# BEP32_90Grad.net
KiCad netlist of a schematic drawn in EAGLE
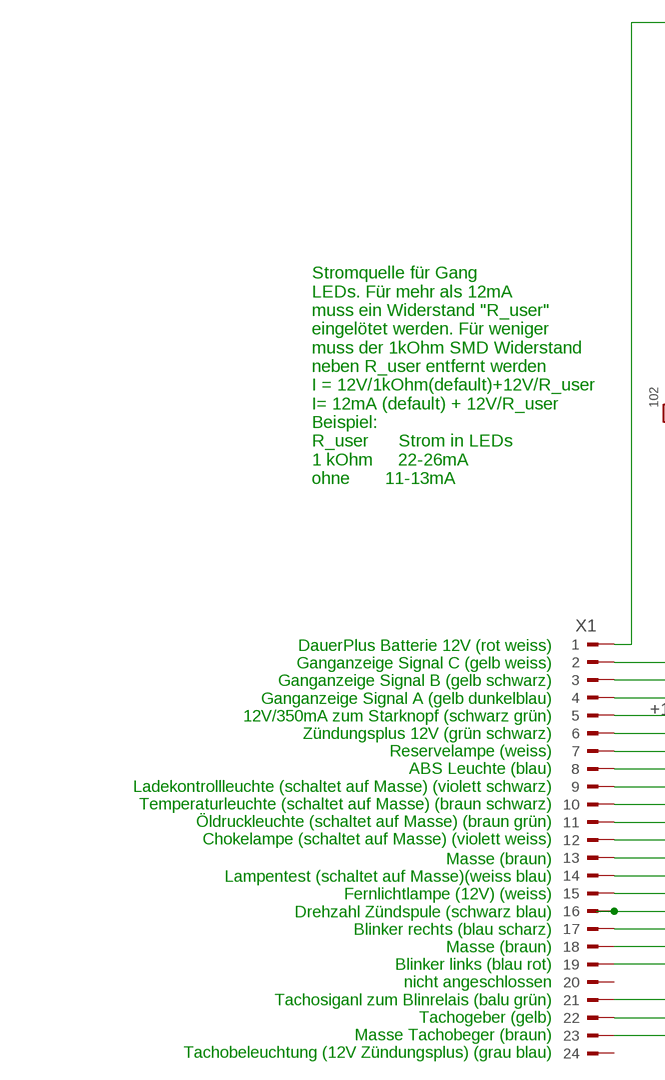
[diagram p0: schematic, sheet 1, part 1 of 2]
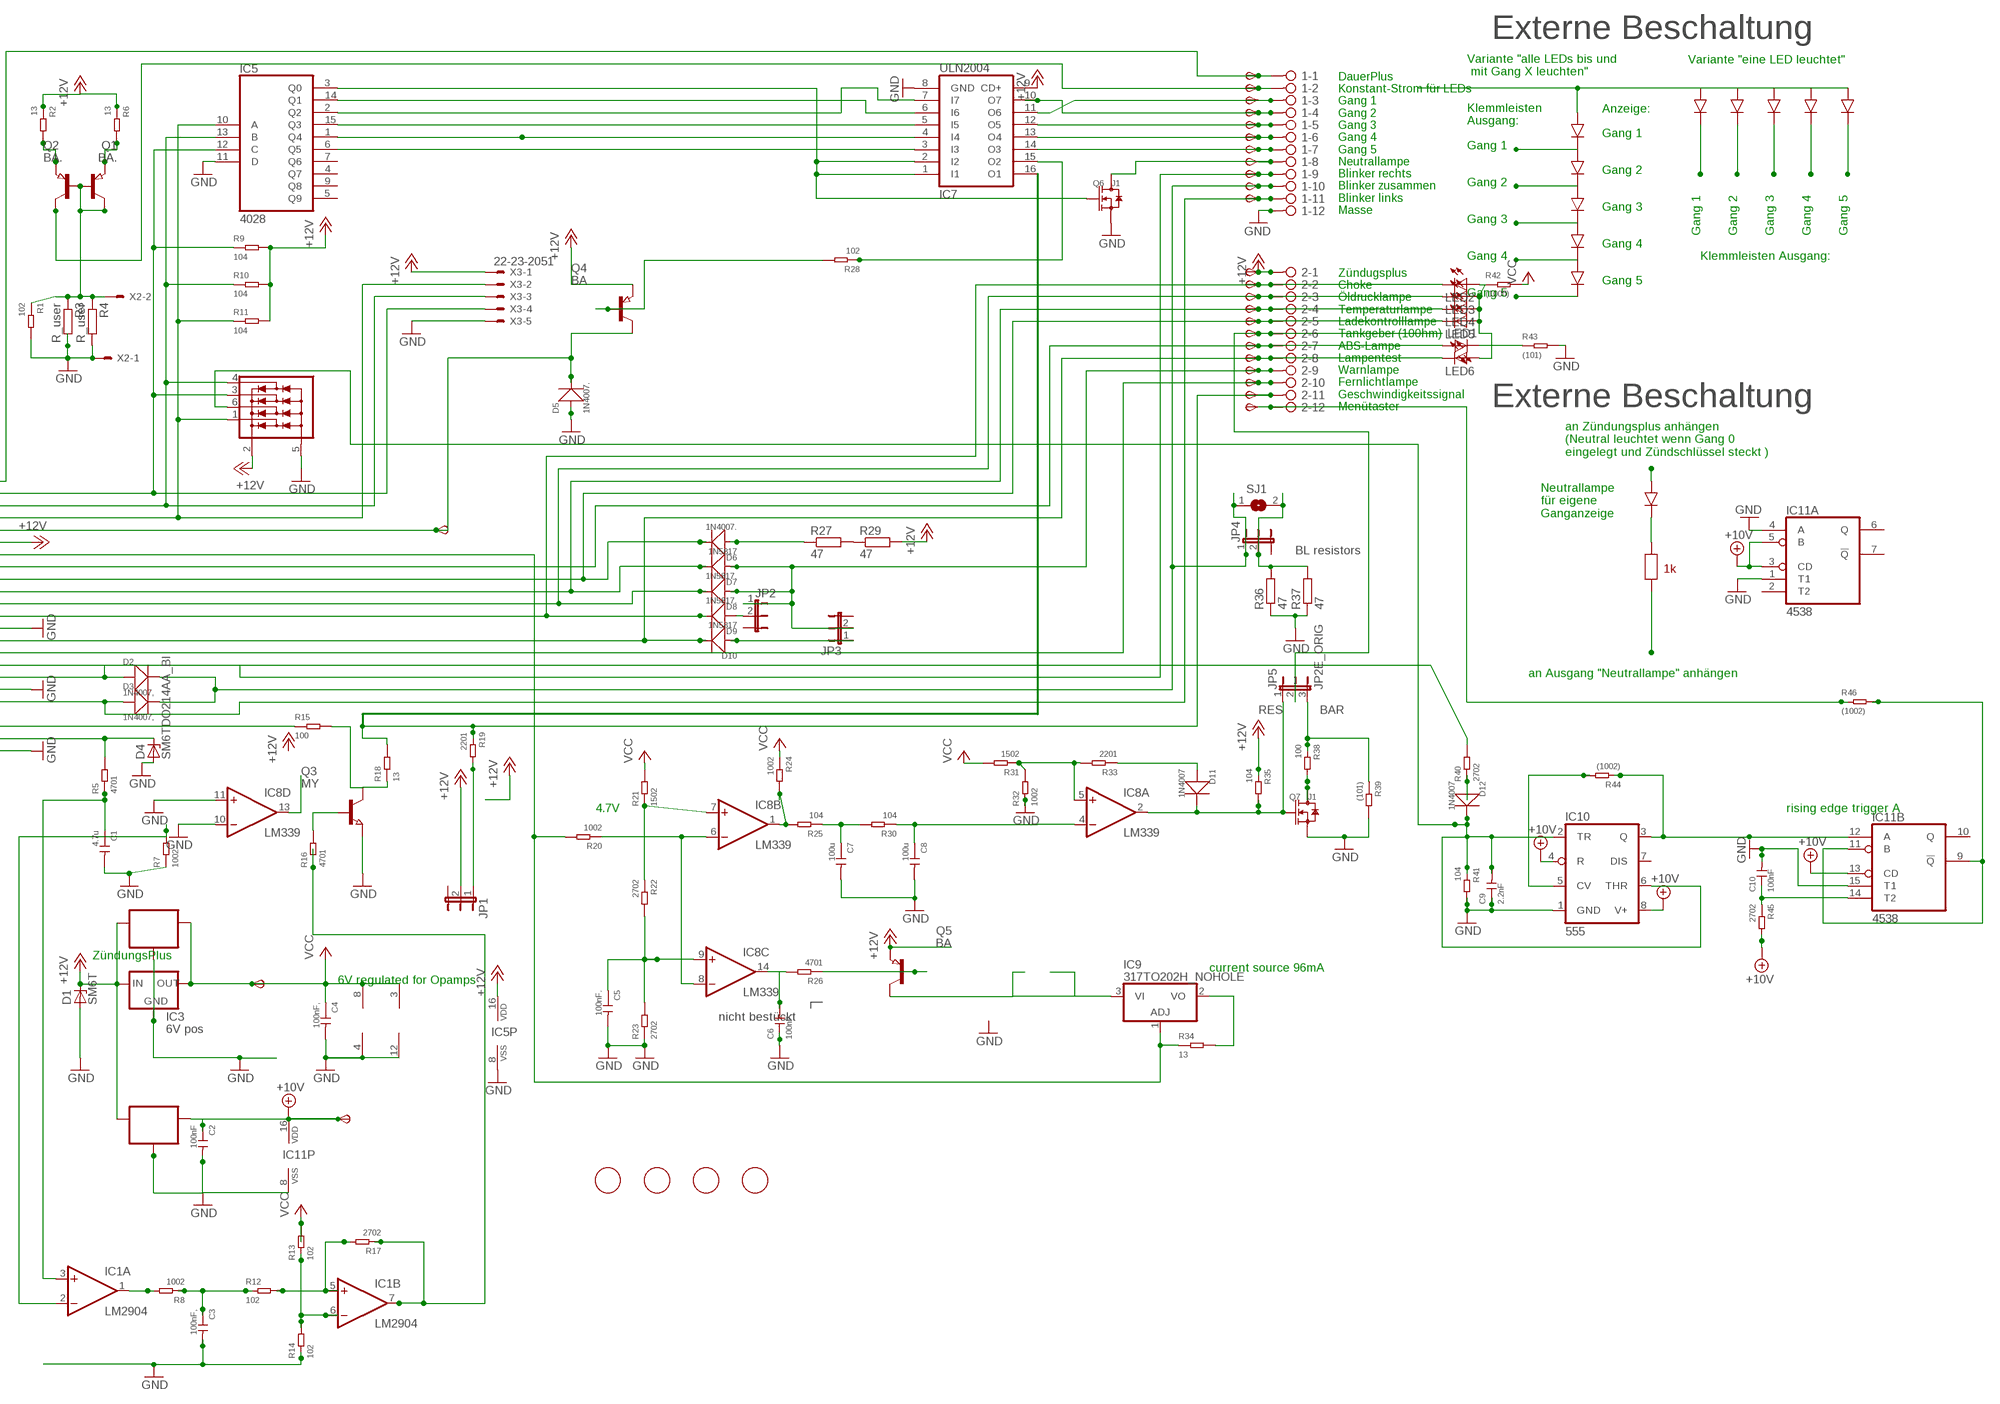
[diagram p1: schematic, sheet 1, part 2 of 2]

(export (version "E")
  (design (tool "Eeschema 10.0.6"))
  (components
    (comp (ref "1")
      (value "2081-1132")
      (footprint "eagle-import:12-PIN")
      (libsource (lib "eagle-import") (part "2081-1132"))
    )
    (comp (ref "2")
      (value "2081-1132")
      (footprint "eagle-import:12-PIN")
      (libsource (lib "eagle-import") (part "2081-1132"))
    )
    (comp (ref "6V")
      (value "TPSB2.0")
      (footprint "eagle-import:B2.0")
      (libsource (lib "eagle-import") (part "TPSB2.0"))
    )
    (comp (ref "10V")
      (value "TPSB2.0")
      (footprint "eagle-import:B2.0")
      (libsource (lib "eagle-import") (part "TPSB2.0"))
    )
    (comp (ref "C1")
      (value "4.7u")
      (footprint "eagle-import:C0805")
      (fields (field (name "MPN") "CC0805KKX5R8BB475"))
      (libsource (lib "eagle-import") (part "CERAMIC-4.7UF-25V-10%-X5R(0805)"))
    )
    (comp (ref "C2")
      (value "100nF")
      (footprint "eagle-import:C0805")
      (fields (field (name "MPN") "CC0805KRX7R9BB104"))
      (libsource (lib "eagle-import") (part "CERAMIC-100NF-50V-10%-X7R(0805)"))
    )
    (comp (ref "C3")
      (value "100nF,")
      (footprint "eagle-import:C0805")
      (fields (field (name "MPN") "CC0805KRX7R9BB104"))
      (libsource (lib "eagle-import") (part "CERAMIC-100NF-50V-10%-X7R(0805)"))
    )
    (comp (ref "C4")
      (value "100nF,")
      (footprint "eagle-import:C0805")
      (fields (field (name "MPN") "CC0805KRX7R9BB104"))
      (libsource (lib "eagle-import") (part "CERAMIC-100NF-50V-10%-X7R(0805)"))
    )
    (comp (ref "C5")
      (value "100nF.")
      (footprint "eagle-import:C0805")
      (fields (field (name "MPN") "CC0805KRX7R9BB104"))
      (libsource (lib "eagle-import") (part "CERAMIC-100NF-50V-10%-X7R(0805)"))
    )
    (comp (ref "C6")
      (value "100nF.")
      (footprint "eagle-import:C0805")
      (fields (field (name "MPN") "CC0805KRX7R9BB104"))
      (libsource (lib "eagle-import") (part "CERAMIC-100NF-50V-10%-X7R(0805)"))
    )
    (comp (ref "C7")
      (value "100u")
      (footprint "eagle-import:C1206")
      (fields (field (name "MPN") "GRM31CR60J107ME39L"))
      (libsource (lib "eagle-import") (part "CERAMIC-100UF-6.3V-20%-X5R(1206)"))
    )
    (comp (ref "C8")
      (value "100u")
      (footprint "eagle-import:C1206")
      (fields (field (name "MPN") "GRM31CR60J107ME39L"))
      (libsource (lib "eagle-import") (part "CERAMIC-100UF-6.3V-20%-X5R(1206)"))
    )
    (comp (ref "C9")
      (value "2.2nF")
      (footprint "eagle-import:C0805")
      (fields (field (name "MPN") "CC0805KRX7R9BB104"))
      (libsource (lib "eagle-import") (part "CERAMIC-100NF-50V-10%-X7R(0805)"))
    )
    (comp (ref "C10")
      (value "100nF")
      (footprint "eagle-import:C0805")
      (fields (field (name "MPN") "CC0805KRX7R9BB104"))
      (libsource (lib "eagle-import") (part "CERAMIC-100NF-50V-10%-X7R(0805)"))
    )
    (comp (ref "D1")
      (value "SM6T")
      (footprint "eagle-import:DO214AA")
      (libsource (lib "eagle-import") (part "SM6T"))
    )
    (comp (ref "D2")
      (value "1N4007,")
      (footprint "eagle-import:DO-214AC")
      (fields (field (name "MPN") "1N4007"))
      (libsource (lib "eagle-import") (part "DIODE-GEN-PURPOSE-1KV-1A(DO-214AC)"))
    )
    (comp (ref "D3")
      (value "1N4007,")
      (footprint "eagle-import:DO-214AC")
      (fields (field (name "MPN") "1N4007"))
      (libsource (lib "eagle-import") (part "DIODE-GEN-PURPOSE-1KV-1A(DO-214AC)"))
    )
    (comp (ref "D4")
      (value "SM6TDO214AA_BI")
      (footprint "eagle-import:DO214AA_BI")
      (libsource (lib "eagle-import") (part "SM6TDO214AA_BI"))
    )
    (comp (ref "D5")
      (value "1N4007.")
      (footprint "eagle-import:DO-214AC")
      (fields (field (name "MPN") "1N4007"))
      (libsource (lib "eagle-import") (part "DIODE-GEN-PURPOSE-1KV-1A(DO-214AC)"))
    )
    (comp (ref "D6")
      (value "1N4007.")
      (footprint "eagle-import:DO-214AC")
      (fields (field (name "MPN") "1N4007"))
      (libsource (lib "eagle-import") (part "DIODE-GEN-PURPOSE-1KV-1A(DO-214AC)"))
    )
    (comp (ref "D7")
      (value "1N5817")
      (footprint "eagle-import:DO-214AC_SLIM")
      (libsource (lib "eagle-import") (part "DIODE-GEN-PURPOSE-1KV-1A(DO-214AC)DO-214AC/1206"))
    )
    (comp (ref "D8")
      (value "1N5817.")
      (footprint "eagle-import:DO-214AC_SLIM")
      (libsource (lib "eagle-import") (part "DIODE-GEN-PURPOSE-1KV-1A(DO-214AC)DO-214AC/1206"))
    )
    (comp (ref "D9")
      (value "1N5817.")
      (footprint "eagle-import:DO-214AC_SLIM")
      (libsource (lib "eagle-import") (part "DIODE-GEN-PURPOSE-1KV-1A(DO-214AC)DO-214AC/1206"))
    )
    (comp (ref "D10")
      (value "1N5817")
      (footprint "eagle-import:DO-214AC_SLIM")
      (libsource (lib "eagle-import") (part "DIODE-GEN-PURPOSE-1KV-1A(DO-214AC)DO-214AC/1206"))
    )
    (comp (ref "D11")
      (value "1N4007")
      (footprint "eagle-import:DO-214AC")
      (libsource (lib "eagle-import") (part "DIODE-GEN-PURPOSE-1KV-1A(DO-214AC)"))
    )
    (comp (ref "D12")
      (value "1N4007")
      (footprint "eagle-import:DO-214AC")
      (libsource (lib "eagle-import") (part "DIODE-GEN-PURPOSE-1KV-1A(DO-214AC)"))
    )
    (comp (ref "FID1")
      (value "FIDUCIAL")
      (footprint "eagle-import:FIDUCIAL_1MM")
      (libsource (lib "eagle-import") (part "FIDUCIAL"))
    )
    (comp (ref "FID2")
      (value "FIDUCIAL")
      (footprint "eagle-import:FIDUCIAL_1MM")
      (libsource (lib "eagle-import") (part "FIDUCIAL"))
    )
    (comp (ref "FID3")
      (value "FIDUCIAL")
      (footprint "eagle-import:FIDUCIAL_1MM")
      (libsource (lib "eagle-import") (part "FIDUCIAL"))
    )
    (comp (ref "FID4")
      (value "FIDUCIAL")
      (footprint "eagle-import:FIDUCIAL_1MM")
      (libsource (lib "eagle-import") (part "FIDUCIAL"))
    )
    (comp (ref "IC1")
      (value "LM2904")
      (footprint "eagle-import:SO08")
      (libsource (lib "eagle-import") (part "LM358D"))
    )
    (comp (ref "IC2")
      (value "78L06")
      (footprint "eagle-import:SOT89_ROUND")
      (libsource (lib "eagle-import") (part "78LXXSOT89_ROUND"))
    )
    (comp (ref "IC3")
      (value "6V pos")
      (footprint "eagle-import:78LXX")
      (libsource (lib "eagle-import") (part "v-reg_78LXX"))
    )
    (comp (ref "IC4")
      (value "78L10")
      (footprint "eagle-import:SOT89_ROUND")
      (libsource (lib "eagle-import") (part "78LXXSOT89_ROUND"))
    )
    (comp (ref "IC5")
      (value "4028")
      (footprint "eagle-import:SO16")
      (libsource (lib "eagle-import") (part "4028D"))
    )
    (comp (ref "IC6")
      (value "NUP4304SOT457_R")
      (footprint "eagle-import:SOT457R_PHILIPS")
      (libsource (lib "eagle-import") (part "NUP4304SOT457_R"))
    )
    (comp (ref "IC7")
      (value "ULN2004")
      (footprint "eagle-import:SO16")
      (libsource (lib "eagle-import") (part "ULN2004AD"))
    )
    (comp (ref "IC8")
      (value "LM339")
      (footprint "eagle-import:SO14")
      (libsource (lib "eagle-import") (part "LM339D"))
    )
    (comp (ref "IC9")
      (value "317TO202H_NOHOLE")
      (footprint "eagle-import:TO220H_NOHOLE")
      (libsource (lib "eagle-import") (part "317TO202H_NOHOLE"))
    )
    (comp (ref "IC10")
      (value "555")
      (footprint "eagle-import:SO08")
      (libsource (lib "eagle-import") (part "555DNE"))
    )
    (comp (ref "IC11")
      (value "4538")
      (footprint "eagle-import:SO16")
      (libsource (lib "eagle-import") (part "4538D"))
    )
    (comp (ref "JP1")
      (value "JP2EJP2_SMALLPADS")
      (footprint "eagle-import:JP2_SMALLPADS")
      (libsource (lib "eagle-import") (part "JP2EJP2_SMALLPADS"))
    )
    (comp (ref "JP2")
      (value "JP2EJP2_SMALLPADS")
      (footprint "eagle-import:JP2_SMALLPADS")
      (libsource (lib "eagle-import") (part "JP2EJP2_SMALLPADS"))
    )
    (comp (ref "JP3")
      (value "JP2EJP2_SMALLPADS")
      (footprint "eagle-import:JP2_SMALLPADS")
      (libsource (lib "eagle-import") (part "JP2EJP2_SMALLPADS"))
    )
    (comp (ref "JP4")
      (value "JP2EJP2_SMALLPADS")
      (footprint "eagle-import:JP2_SMALLPADS")
      (libsource (lib "eagle-import") (part "JP2EJP2_SMALLPADS"))
    )
    (comp (ref "JP5")
      (value "JP2E_ORIG")
      (footprint "eagle-import:JP2_ORIG_SMALLPADS")
      (libsource (lib "eagle-import") (part "JP2E_ORIG"))
    )
    (comp (ref "LED1")
      (value "LEDLD260")
      (footprint "eagle-import:LD260")
      (libsource (lib "eagle-import") (part "LEDLD260"))
    )
    (comp (ref "LED2")
      (value "LEDLD260")
      (footprint "eagle-import:LD260")
      (libsource (lib "eagle-import") (part "LEDLD260"))
    )
    (comp (ref "LED3")
      (value "LEDLD260")
      (footprint "eagle-import:LD260")
      (libsource (lib "eagle-import") (part "LEDLD260"))
    )
    (comp (ref "LED4")
      (value "LEDLD260")
      (footprint "eagle-import:LD260")
      (libsource (lib "eagle-import") (part "LEDLD260"))
    )
    (comp (ref "LED5")
      (value "LEDLD260")
      (footprint "eagle-import:LD260")
      (libsource (lib "eagle-import") (part "LEDLD260"))
    )
    (comp (ref "LED6")
      (value "LEDLD260")
      (footprint "eagle-import:LD260")
      (libsource (lib "eagle-import") (part "LEDLD260"))
    )
    (comp (ref "Q1")
      (value "BA.")
      (footprint "eagle-import:SOT89")
      (libsource (lib "eagle-import") (part "PNP-TRANSISTOR_SOT89"))
    )
    (comp (ref "Q2")
      (value "BA.")
      (footprint "eagle-import:SOT89")
      (libsource (lib "eagle-import") (part "PNP-TRANSISTOR_SOT89"))
    )
    (comp (ref "Q3")
      (value "MY")
      (footprint "eagle-import:SOT89")
      (libsource (lib "eagle-import") (part "NPN-TRANSISTOR_SOT89"))
    )
    (comp (ref "Q4")
      (value "BA")
      (footprint "eagle-import:SOT89")
      (libsource (lib "eagle-import") (part "PNP-TRANSISTOR_SOT89"))
    )
    (comp (ref "Q5")
      (value "BA")
      (footprint "eagle-import:SOT89")
      (libsource (lib "eagle-import") (part "PNP-TRANSISTOR_SOT89"))
    )
    (comp (ref "Q6")
      (value "J1")
      (footprint "eagle-import:SOT-23")
      (fields (field (name "MPN") "BSS138W-7-F"))
      (libsource (lib "eagle-import") (part "SMD-MOSFET-N-CH-50V-200MA-BSS138W-7-F(SOT-23)"))
    )
    (comp (ref "Q7")
      (value "J1")
      (footprint "eagle-import:SOT-23")
      (fields (field (name "MPN") "BSS138W-7-F"))
      (libsource (lib "eagle-import") (part "SMD-MOSFET-N-CH-50V-200MA-BSS138W-7-F(SOT-23)"))
    )
    (comp (ref "R1")
      (value "102")
      (footprint "eagle-import:R0805")
      (fields (field (name "MPN") "RC0805JR-071KL"))
      (libsource (lib "eagle-import") (part "SMD-RES-1K-5%-1/8W(0805)"))
    )
    (comp (ref "R2")
      (value "13")
      (footprint "eagle-import:R1206")
      (fields (field (name "MPN") "RC1206JR-0713RL"))
      (libsource (lib "eagle-import") (part "SMD-RES-13R-5%-1/4W(1206)"))
    )
    (comp (ref "R3")
      (value "R_user")
      (footprint "eagle-import:R0805")
      (libsource (lib "eagle-import") (part "R-EU_R0805"))
    )
    (comp (ref "R4")
      (value "R_user")
      (footprint "eagle-import:R0805")
      (libsource (lib "eagle-import") (part "R-EU_R0805"))
    )
    (comp (ref "R5")
      (value "4701")
      (footprint "eagle-import:R0805")
      (fields (field (name "MPN") "RC0805JR-074K7L"))
      (libsource (lib "eagle-import") (part "SMD-RES-4.7K-5%-1/8W(0805)"))
    )
    (comp (ref "R6")
      (value "13")
      (footprint "eagle-import:R1206")
      (fields (field (name "MPN") "RC1206JR-0713RL"))
      (libsource (lib "eagle-import") (part "SMD-RES-13R-5%-1/4W(1206)"))
    )
    (comp (ref "R7")
      (value "1002")
      (footprint "eagle-import:R0805")
      (fields (field (name "MPN") "RC0805FR-0710KL"))
      (libsource (lib "eagle-import") (part "SMD-RES-10K-1%-1/8W(0805)"))
    )
    (comp (ref "R8")
      (value "1002")
      (footprint "eagle-import:R0805")
      (fields (field (name "MPN") "RC0805FR-0710KL"))
      (libsource (lib "eagle-import") (part "SMD-RES-10K-1%-1/8W(0805)"))
    )
    (comp (ref "R9")
      (value "104")
      (footprint "eagle-import:R0805")
      (fields (field (name "MPN") "RC0805FR-0710KL"))
      (libsource (lib "eagle-import") (part "SMD-RES-10K-1%-1/8W(0805)"))
    )
    (comp (ref "R10")
      (value "104")
      (footprint "eagle-import:R0805")
      (fields (field (name "MPN") "RC0805FR-0710KL"))
      (libsource (lib "eagle-import") (part "SMD-RES-10K-1%-1/8W(0805)"))
    )
    (comp (ref "R11")
      (value "104")
      (footprint "eagle-import:R0805")
      (fields (field (name "MPN") "RC0805FR-0710KL"))
      (libsource (lib "eagle-import") (part "SMD-RES-10K-1%-1/8W(0805)"))
    )
    (comp (ref "R12")
      (value "102")
      (footprint "eagle-import:R0805")
      (fields (field (name "MPN") "RC0805JR-071KL"))
      (libsource (lib "eagle-import") (part "SMD-RES-1K-5%-1/8W(0805)"))
    )
    (comp (ref "R13")
      (value "102")
      (footprint "eagle-import:R0805")
      (fields (field (name "MPN") "RC0805JR-071KL"))
      (libsource (lib "eagle-import") (part "SMD-RES-1K-5%-1/8W(0805)"))
    )
    (comp (ref "R14")
      (value "102")
      (footprint "eagle-import:R0805")
      (fields (field (name "MPN") "RC0805JR-071KL"))
      (libsource (lib "eagle-import") (part "SMD-RES-1K-5%-1/8W(0805)"))
    )
    (comp (ref "R15")
      (value "100")
      (footprint "eagle-import:R0805")
      (fields (field (name "MPN") "RC0805JR-07220RL"))
      (libsource (lib "eagle-import") (part "SMD-RES-220R-5%-1/8W(0805)"))
    )
    (comp (ref "R16")
      (value "4701")
      (footprint "eagle-import:R0805")
      (fields (field (name "MPN") "RC0805JR-074K7L"))
      (libsource (lib "eagle-import") (part "SMD-RES-4.7K-5%-1/8W(0805)"))
    )
    (comp (ref "R17")
      (value "2702")
      (footprint "eagle-import:R0805")
      (fields (field (name "MPN") "RC0805JR-074K7L"))
      (libsource (lib "eagle-import") (part "SMD-RES-4.7K-5%-1/8W(0805)"))
    )
    (comp (ref "R18")
      (value "13")
      (footprint "eagle-import:R1206")
      (fields (field (name "MPN") "RC1206JR-0713RL"))
      (libsource (lib "eagle-import") (part "SMD-RES-13R-5%-1/4W(1206)"))
    )
    (comp (ref "R19")
      (value "2201")
      (footprint "eagle-import:R0805")
      (fields (field (name "MPN") "RC0805JR-072K2L"))
      (libsource (lib "eagle-import") (part "SMD-RES-2.2K-5%-1/8W(0805)"))
    )
    (comp (ref "R20")
      (value "1002")
      (footprint "eagle-import:R0805")
      (fields (field (name "MPN") "RC0805FR-0710KL"))
      (libsource (lib "eagle-import") (part "SMD-RES-10K-1%-1/8W(0805)"))
    )
    (comp (ref "R21")
      (value "1502")
      (footprint "eagle-import:R0805")
      (fields (field (name "MPN") "RC0805FR-0710KL"))
      (libsource (lib "eagle-import") (part "SMD-RES-10K-1%-1/8W(0805)"))
    )
    (comp (ref "R22")
      (value "2702")
      (footprint "eagle-import:R0805")
      (fields (field (name "MPN") "RC0805JR-074K7L"))
      (libsource (lib "eagle-import") (part "SMD-RES-4.7K-5%-1/8W(0805)"))
    )
    (comp (ref "R23")
      (value "2702")
      (footprint "eagle-import:R0805")
      (fields (field (name "MPN") "RC0805JR-074K7L"))
      (libsource (lib "eagle-import") (part "SMD-RES-4.7K-5%-1/8W(0805)"))
    )
    (comp (ref "R24")
      (value "1002")
      (footprint "eagle-import:R0805")
      (fields (field (name "MPN") "RC0805FR-0710KL"))
      (libsource (lib "eagle-import") (part "SMD-RES-10K-1%-1/8W(0805)"))
    )
    (comp (ref "R25")
      (value "104")
      (footprint "eagle-import:R0805")
      (fields (field (name "MPN") "RC0805FR-0710KL"))
      (libsource (lib "eagle-import") (part "SMD-RES-10K-1%-1/8W(0805)"))
    )
    (comp (ref "R26")
      (value "4701")
      (footprint "eagle-import:R0805")
      (fields (field (name "MPN") "RC0805JR-074K7L"))
      (libsource (lib "eagle-import") (part "SMD-RES-4.7K-5%-1/8W(0805)"))
    )
    (comp (ref "R27")
      (value "47")
      (footprint "eagle-import:V235_17_1MM")
      (libsource (lib "eagle-import") (part "R-EU_V235/17_1MM"))
    )
    (comp (ref "R28")
      (value "102")
      (footprint "eagle-import:R0805")
      (fields (field (name "MPN") "RC0805JR-071KL"))
      (libsource (lib "eagle-import") (part "SMD-RES-1K-5%-1/8W(0805)"))
    )
    (comp (ref "R29")
      (value "47")
      (footprint "eagle-import:V235_17_1MM")
      (libsource (lib "eagle-import") (part "R-EU_V235/17_1MM"))
    )
    (comp (ref "R30")
      (value "104")
      (footprint "eagle-import:R0805")
      (fields (field (name "MPN") "RC0805FR-0710KL"))
      (libsource (lib "eagle-import") (part "SMD-RES-10K-1%-1/8W(0805)"))
    )
    (comp (ref "R31")
      (value "1502")
      (footprint "eagle-import:R0805")
      (fields (field (name "MPN") "RC0805FR-0710KL"))
      (libsource (lib "eagle-import") (part "SMD-RES-10K-1%-1/8W(0805)"))
    )
    (comp (ref "R32")
      (value "1002")
      (footprint "eagle-import:R0805")
      (fields (field (name "MPN") "RC0805FR-0710KL"))
      (libsource (lib "eagle-import") (part "SMD-RES-10K-1%-1/8W(0805)"))
    )
    (comp (ref "R33")
      (value "2201")
      (footprint "eagle-import:R0805")
      (fields (field (name "MPN") "RC0805JR-072K2L"))
      (libsource (lib "eagle-import") (part "SMD-RES-2.2K-5%-1/8W(0805)"))
    )
    (comp (ref "R34")
      (value "13")
      (footprint "eagle-import:R1206")
      (fields (field (name "MPN") "RC1206JR-0713RL"))
      (libsource (lib "eagle-import") (part "SMD-RES-13R-5%-1/4W(1206)"))
    )
    (comp (ref "R35")
      (value "104")
      (footprint "eagle-import:R0805")
      (fields (field (name "MPN") "RC0805FR-0710KL"))
      (libsource (lib "eagle-import") (part "SMD-RES-10K-1%-1/8W(0805)"))
    )
    (comp (ref "R36")
      (value "47")
      (footprint "eagle-import:V235_17_1MM")
      (libsource (lib "eagle-import") (part "R-EU_V235/17_1MM"))
    )
    (comp (ref "R37")
      (value "47")
      (footprint "eagle-import:V235_17_1MM")
      (libsource (lib "eagle-import") (part "R-EU_V235/17_1MM"))
    )
    (comp (ref "R38")
      (value "100")
      (footprint "eagle-import:R0805")
      (fields (field (name "MPN") "RC0805JR-072K2L"))
      (libsource (lib "eagle-import") (part "SMD-RES-2.2K-5%-1/8W(0805)"))
    )
    (comp (ref "R39")
      (value "(101)")
      (footprint "eagle-import:R0805")
      (fields (field (name "MPN") "RC0805JR-072K2L"))
      (libsource (lib "eagle-import") (part "SMD-RES-2.2K-5%-1/8W(0805)"))
    )
    (comp (ref "R40")
      (value "2702")
      (footprint "eagle-import:R0805")
      (fields (field (name "MPN") "RC0805FR-0710KL"))
      (libsource (lib "eagle-import") (part "SMD-RES-10K-1%-1/8W(0805)"))
    )
    (comp (ref "R41")
      (value "104")
      (footprint "eagle-import:R0805")
      (fields (field (name "MPN") "RC0805FR-0710KL"))
      (libsource (lib "eagle-import") (part "SMD-RES-10K-1%-1/8W(0805)"))
    )
    (comp (ref "R42")
      (value "(1000)")
      (footprint "eagle-import:R0805")
      (fields (field (name "MPN") "RC0805JR-07100RL"))
      (libsource (lib "eagle-import") (part "SMD-RES-100R-5%-1/8W(0805)"))
    )
    (comp (ref "R43")
      (value "(101)")
      (footprint "eagle-import:R0805")
      (fields (field (name "MPN") "RC0805JR-07100RL"))
      (libsource (lib "eagle-import") (part "SMD-RES-100R-5%-1/8W(0805)"))
    )
    (comp (ref "R44")
      (value "(1002)")
      (footprint "eagle-import:R0805")
      (fields (field (name "MPN") "RC0805FR-0710KL"))
      (libsource (lib "eagle-import") (part "SMD-RES-10K-1%-1/8W(0805)"))
    )
    (comp (ref "R45")
      (value "2702")
      (footprint "eagle-import:R0805")
      (fields (field (name "MPN") "RC0805JR-074K7L"))
      (libsource (lib "eagle-import") (part "SMD-RES-4.7K-5%-1/8W(0805)"))
    )
    (comp (ref "R46")
      (value "(1002)")
      (footprint "eagle-import:R0805")
      (fields (field (name "MPN") "RC0805JR-074K7L"))
      (libsource (lib "eagle-import") (part "SMD-RES-4.7K-5%-1/8W(0805)"))
    )
    (comp (ref "SJ1") (value "SJ") (footprint "eagle-import:SJ") (libsource (lib "eagle-import") (part "SJ")))
    (comp (ref "START")
      (value "TPSB2.0")
      (footprint "eagle-import:B2.0")
      (libsource (lib "eagle-import") (part "TPSB2.0"))
    )
    (comp (ref "TP1")
      (value "TPSB2.0")
      (footprint "eagle-import:B2.0")
      (libsource (lib "eagle-import") (part "TPSB2.0"))
    )
    (comp (ref "TP2")
      (value "TPSB2.0")
      (footprint "eagle-import:B2.0")
      (libsource (lib "eagle-import") (part "TPSB2.0"))
    )
    (comp (ref "TP3")
      (value "TPSB2.0")
      (footprint "eagle-import:B2.0")
      (libsource (lib "eagle-import") (part "TPSB2.0"))
    )
    (comp (ref "TP4")
      (value "TPSB2.0")
      (footprint "eagle-import:B2.0")
      (libsource (lib "eagle-import") (part "TPSB2.0"))
    )
    (comp (ref "TP5")
      (value "TPSB2.0")
      (footprint "eagle-import:B2.0")
      (libsource (lib "eagle-import") (part "TPSB2.0"))
    )
    (comp (ref "TP6")
      (value "TPSB2.0")
      (footprint "eagle-import:B2.0")
      (libsource (lib "eagle-import") (part "TPSB2.0"))
    )
    (comp (ref "TP7")
      (value "TPSB2.0")
      (footprint "eagle-import:B2.0")
      (libsource (lib "eagle-import") (part "TPSB2.0"))
    )
    (comp (ref "TP8")
      (value "TPSB2.0")
      (footprint "eagle-import:B2.0")
      (libsource (lib "eagle-import") (part "TPSB2.0"))
    )
    (comp (ref "TP9")
      (value "TPSB2.0")
      (footprint "eagle-import:B2.0")
      (libsource (lib "eagle-import") (part "TPSB2.0"))
    )
    (comp (ref "TP10")
      (value "TPSB2.0")
      (footprint "eagle-import:B2.0")
      (libsource (lib "eagle-import") (part "TPSB2.0"))
    )
    (comp (ref "TP11")
      (value "TPSB2.0")
      (footprint "eagle-import:B2.0")
      (libsource (lib "eagle-import") (part "TPSB2.0"))
    )
    (comp (ref "TP12")
      (value "TPSB2.0")
      (footprint "eagle-import:B2.0")
      (libsource (lib "eagle-import") (part "TPSB2.0"))
    )
    (comp (ref "TP13")
      (value "TPSB2.0")
      (footprint "eagle-import:B2.0")
      (libsource (lib "eagle-import") (part "TPSB2.0"))
    )
    (comp (ref "TP16")
      (value "TPSB2.0")
      (footprint "eagle-import:B2.0")
      (libsource (lib "eagle-import") (part "TPSB2.0"))
    )
    (comp (ref "TP17")
      (value "TPSB2.0")
      (footprint "eagle-import:B2.0")
      (libsource (lib "eagle-import") (part "TPSB2.0"))
    )
    (comp (ref "TP18")
      (value "TPSB2.0")
      (footprint "eagle-import:B2.0")
      (libsource (lib "eagle-import") (part "TPSB2.0"))
    )
    (comp (ref "TP19")
      (value "TPSB2.0")
      (footprint "eagle-import:B2.0")
      (libsource (lib "eagle-import") (part "TPSB2.0"))
    )
    (comp (ref "TP21")
      (value "TPSB2.0")
      (footprint "eagle-import:B2.0")
      (libsource (lib "eagle-import") (part "TPSB2.0"))
    )
    (comp (ref "TP22")
      (value "TPSB2.0")
      (footprint "eagle-import:B2.0")
      (libsource (lib "eagle-import") (part "TPSB2.0"))
    )
    (comp (ref "TP23")
      (value "TPSB2.0")
      (footprint "eagle-import:B2.0")
      (libsource (lib "eagle-import") (part "TPSB2.0"))
    )
    (comp (ref "TP24")
      (value "TPSB1,27")
      (footprint "eagle-import:B1,27")
      (libsource (lib "eagle-import") (part "TPSB1,27"))
    )
    (comp (ref "TP25")
      (value "TPSB2.0")
      (footprint "eagle-import:B2.0")
      (libsource (lib "eagle-import") (part "TPSB2.0"))
    )
    (comp (ref "TP26")
      (value "TPSB2.0")
      (footprint "eagle-import:B2.0")
      (libsource (lib "eagle-import") (part "TPSB2.0"))
    )
    (comp (ref "X1")
      (value "CON_BMWV2")
      (footprint "eagle-import:24-PIN_V2")
      (libsource (lib "eagle-import") (part "CON_BMWV2"))
    )
    (comp (ref "X2")
      (value "22-23-2021")
      (footprint "eagle-import:22-23-2021")
      (fields (field (name "MF") "MOLEX"))
      (libsource (lib "eagle-import") (part "22-23-2021"))
    )
    (comp (ref "X3")
      (value "22-23-2051")
      (footprint "eagle-import:22-23-2051")
      (fields (field (name "MF") "MOLEX"))
      (libsource (lib "eagle-import") (part "22-23-2051"))
    )
  )
  (nets
    (net (code "1") (name "+10V") (class "Default")
      (node (ref "10V") (pin "TP") (pinfunction "PP_TP") (pintype "input"))
      (node (ref "C2") (pin "1") (pinfunction "1_1") (pintype "passive"))
      (node (ref "IC10") (pin "4") (pinfunction "R_4") (pintype "input"))
      (node (ref "IC10") (pin "8") (pinfunction "V+_8") (pintype "power_in"))
      (node (ref "IC11") (pin "13") (pinfunction "CD_13") (pintype "input"))
      (node (ref "IC11") (pin "16") (pinfunction "VDD_16") (pintype "power_in"))
      (node (ref "IC11") (pin "3") (pinfunction "CD_3") (pintype "input"))
      (node (ref "IC11") (pin "5") (pinfunction "B_5") (pintype "input"))
      (node (ref "IC4") (pin "1") (pinfunction "OUT_1") (pintype "passive"))
      (node (ref "R45") (pin "2") (pinfunction "2_2") (pintype "passive"))
    )
    (net (code "2") (name "+12V") (class "Default")
      (node (ref "2") (pin "1") (pinfunction "KL_1") (pintype "passive"))
      (node (ref "D1") (pin "C") (pinfunction "C_C") (pintype "passive"))
      (node (ref "IC2") (pin "3") (pinfunction "IN_3") (pintype "input"))
      (node (ref "IC3") (pin "IN") (pinfunction "IN_IN") (pintype "input"))
      (node (ref "IC4") (pin "3") (pinfunction "IN_3") (pintype "input"))
      (node (ref "IC5") (pin "16") (pinfunction "VDD_16") (pintype "power_in"))
      (node (ref "IC6") (pin "2") (pinfunction "V+_2") (pintype "passive"))
      (node (ref "IC7") (pin "9") (pinfunction "CD+_9") (pintype "passive"))
      (node (ref "JP1") (pin "2") (pinfunction "2_2") (pintype "passive"))
      (node (ref "Q4") (pin "3") (pinfunction "E_3") (pintype "passive"))
      (node (ref "Q5") (pin "3") (pinfunction "E_3") (pintype "passive"))
      (node (ref "R10") (pin "2") (pinfunction "2_2") (pintype "passive"))
      (node (ref "R11") (pin "2") (pinfunction "2_2") (pintype "passive"))
      (node (ref "R2") (pin "1") (pinfunction "1_1") (pintype "passive"))
      (node (ref "R29") (pin "2") (pinfunction "2_2") (pintype "passive"))
      (node (ref "R35") (pin "1") (pinfunction "1_1") (pintype "passive"))
      (node (ref "R6") (pin "1") (pinfunction "1_1") (pintype "passive"))
      (node (ref "R9") (pin "2") (pinfunction "2_2") (pintype "passive"))
      (node (ref "TP12") (pin "TP") (pinfunction "PP_TP") (pintype "input"))
      (node (ref "X1") (pin "6") (pinfunction "6_6") (pintype "passive"))
      (node (ref "X3") (pin "1") (pinfunction "S_1") (pintype "passive"))
    )
    (net (code "3") (name "GND") (class "Default")
      (node (ref "1") (pin "12") (pinfunction "KL_12") (pintype "passive"))
      (node (ref "C1") (pin "2") (pinfunction "2_2") (pintype "passive"))
      (node (ref "C10") (pin "2") (pinfunction "2_2") (pintype "passive"))
      (node (ref "C2") (pin "2") (pinfunction "2_2") (pintype "passive"))
      (node (ref "C3") (pin "2") (pinfunction "2_2") (pintype "passive"))
      (node (ref "C4") (pin "2") (pinfunction "2_2") (pintype "passive"))
      (node (ref "C5") (pin "2") (pinfunction "2_2") (pintype "passive"))
      (node (ref "C6") (pin "1") (pinfunction "1_1") (pintype "passive"))
      (node (ref "C7") (pin "2") (pinfunction "2_2") (pintype "passive"))
      (node (ref "C8") (pin "2") (pinfunction "2_2") (pintype "passive"))
      (node (ref "C9") (pin "1") (pinfunction "1_1") (pintype "passive"))
      (node (ref "D1") (pin "A") (pinfunction "A_A") (pintype "passive"))
      (node (ref "D4") (pin "A") (pinfunction "A_A") (pintype "passive"))
      (node (ref "D5") (pin "1") (pinfunction "+_1") (pintype "passive"))
      (node (ref "IC1") (pin "4") (pinfunction "V-_4") (pintype "power_in"))
      (node (ref "IC10") (pin "1") (pinfunction "GND_1") (pintype "power_in"))
      (node (ref "IC11") (pin "1") (pinfunction "T1_1") (pintype "input"))
      (node (ref "IC11") (pin "15") (pinfunction "T1_15") (pintype "input"))
      (node (ref "IC11") (pin "4") (pinfunction "A_4") (pintype "input"))
      (node (ref "IC11") (pin "8") (pinfunction "VSS_8") (pintype "power_in"))
      (node (ref "IC2") (pin "2") (pinfunction "GND_2") (pintype "input"))
      (node (ref "IC2") (pin "2@1") (pinfunction "GND_2@1") (pintype "input"))
      (node (ref "IC3") (pin "GND") (pinfunction "GND_GND") (pintype "input"))
      (node (ref "IC4") (pin "2") (pinfunction "GND_2") (pintype "input"))
      (node (ref "IC4") (pin "2@1") (pinfunction "GND_2@1") (pintype "input"))
      (node (ref "IC5") (pin "11") (pinfunction "D_11") (pintype "input"))
      (node (ref "IC5") (pin "8") (pinfunction "VSS_8") (pintype "power_in"))
      (node (ref "IC6") (pin "5") (pinfunction "V-_5") (pintype "passive"))
      (node (ref "IC7") (pin "8") (pinfunction "GND_8") (pintype "power_in"))
      (node (ref "IC8") (pin "10") (pinfunction "-IN_10") (pintype "input"))
      (node (ref "IC8") (pin "11") (pinfunction "+IN_11") (pintype "input"))
      (node (ref "IC8") (pin "12") (pinfunction "GND_12") (pintype "power_in"))
      (node (ref "Q3") (pin "3") (pinfunction "E_3") (pintype "passive"))
      (node (ref "Q6") (pin "2") (pinfunction "S_2") (pintype "passive"))
      (node (ref "Q7") (pin "2") (pinfunction "S_2") (pintype "passive"))
      (node (ref "R1") (pin "2") (pinfunction "2_2") (pintype "passive"))
      (node (ref "R14") (pin "1") (pinfunction "1_1") (pintype "passive"))
      (node (ref "R23") (pin "1") (pinfunction "1_1") (pintype "passive"))
      (node (ref "R3") (pin "2") (pinfunction "2_2") (pintype "passive"))
      (node (ref "R32") (pin "1") (pinfunction "1_1") (pintype "passive"))
      (node (ref "R36") (pin "1") (pinfunction "1_1") (pintype "passive"))
      (node (ref "R37") (pin "1") (pinfunction "1_1") (pintype "passive"))
      (node (ref "R39") (pin "2") (pinfunction "2_2") (pintype "passive"))
      (node (ref "R4") (pin "2") (pinfunction "2_2") (pintype "passive"))
      (node (ref "R41") (pin "2") (pinfunction "2_2") (pintype "passive"))
      (node (ref "R43") (pin "2") (pinfunction "2_2") (pintype "passive"))
      (node (ref "R7") (pin "1") (pinfunction "1_1") (pintype "passive"))
      (node (ref "X1") (pin "13") (pinfunction "13_13") (pintype "passive"))
      (node (ref "X1") (pin "18") (pinfunction "18_18") (pintype "passive"))
      (node (ref "X1") (pin "23") (pinfunction "23_23") (pintype "passive"))
      (node (ref "X2") (pin "1") (pinfunction "S_1") (pintype "passive"))
      (node (ref "X3") (pin "5") (pinfunction "S_5") (pintype "passive"))
    )
    (net (code "4") (name "Net-(1A-KL)") (class "Default")
      (node (ref "1") (pin "1") (pinfunction "KL_1") (pintype "passive"))
      (node (ref "TP1") (pin "TP") (pinfunction "PP_TP") (pintype "input"))
      (node (ref "X1") (pin "1") (pinfunction "1_1") (pintype "passive"))
    )
    (net (code "5") (name "Net-(1B-KL)") (class "Default")
      (node (ref "1") (pin "10") (pinfunction "KL_10") (pintype "passive"))
      (node (ref "D2") (pin "2") (pinfunction "-_2") (pintype "passive"))
      (node (ref "D3") (pin "2") (pinfunction "-_2") (pintype "passive"))
      (node (ref "JP4") (pin "1") (pinfunction "1_1") (pintype "passive"))
      (node (ref "SJ1") (pin "1") (pinfunction "1_1") (pintype "passive"))
      (node (ref "TP10") (pin "TP") (pinfunction "PP_TP") (pintype "input"))
    )
    (net (code "6") (name "Net-(1C-KL)") (class "Default")
      (node (ref "1") (pin "11") (pinfunction "KL_11") (pintype "passive"))
      (node (ref "D3") (pin "1") (pinfunction "+_1") (pintype "passive"))
      (node (ref "TP11") (pin "TP") (pinfunction "PP_TP") (pintype "input"))
      (node (ref "X1") (pin "19") (pinfunction "19_19") (pintype "passive"))
    )
    (net (code "7") (name "Net-(1E-KL)") (class "Default")
      (node (ref "1") (pin "2") (pinfunction "KL_2") (pintype "passive"))
      (node (ref "Q1") (pin "2") (pinfunction "C_2") (pintype "passive"))
      (node (ref "TP2") (pin "TP") (pinfunction "PP_TP") (pintype "input"))
    )
    (net (code "8") (name "Net-(1F-KL)") (class "Default")
      (node (ref "1") (pin "3") (pinfunction "KL_3") (pintype "passive"))
      (node (ref "IC7") (pin "11") (pinfunction "O6_11") (pintype "open_collector"))
      (node (ref "TP3") (pin "TP") (pinfunction "PP_TP") (pintype "input"))
    )
    (net (code "9") (name "Net-(1G-KL)") (class "Default")
      (node (ref "1") (pin "4") (pinfunction "KL_4") (pintype "passive"))
      (node (ref "IC7") (pin "10") (pinfunction "O7_10") (pintype "open_collector"))
      (node (ref "TP4") (pin "TP") (pinfunction "PP_TP") (pintype "input"))
    )
    (net (code "10") (name "Net-(1H-KL)") (class "Default")
      (node (ref "1") (pin "5") (pinfunction "KL_5") (pintype "passive"))
      (node (ref "IC7") (pin "12") (pinfunction "O5_12") (pintype "open_collector"))
      (node (ref "TP5") (pin "TP") (pinfunction "PP_TP") (pintype "input"))
    )
    (net (code "11") (name "Net-(1I-KL)") (class "Default")
      (node (ref "1") (pin "6") (pinfunction "KL_6") (pintype "passive"))
      (node (ref "IC7") (pin "13") (pinfunction "O4_13") (pintype "open_collector"))
      (node (ref "TP6") (pin "TP") (pinfunction "PP_TP") (pintype "input"))
    )
    (net (code "12") (name "Net-(1J-KL)") (class "Default")
      (node (ref "1") (pin "7") (pinfunction "KL_7") (pintype "passive"))
      (node (ref "IC7") (pin "14") (pinfunction "O3_14") (pintype "open_collector"))
      (node (ref "TP7") (pin "TP") (pinfunction "PP_TP") (pintype "input"))
    )
    (net (code "13") (name "Net-(1K-KL)") (class "Default")
      (node (ref "1") (pin "8") (pinfunction "KL_8") (pintype "passive"))
      (node (ref "Q6") (pin "3") (pinfunction "D_3") (pintype "passive"))
      (node (ref "TP8") (pin "TP") (pinfunction "PP_TP") (pintype "input"))
    )
    (net (code "14") (name "Net-(1L-KL)") (class "Default")
      (node (ref "1") (pin "9") (pinfunction "KL_9") (pintype "passive"))
      (node (ref "D2") (pin "1") (pinfunction "+_1") (pintype "passive"))
      (node (ref "TP9") (pin "TP") (pinfunction "PP_TP") (pintype "input"))
      (node (ref "X1") (pin "17") (pinfunction "17_17") (pintype "passive"))
    )
    (net (code "15") (name "Net-(2B-KL)") (class "Default")
      (node (ref "2") (pin "10") (pinfunction "KL_10") (pintype "passive"))
      (node (ref "TP25") (pin "TP") (pinfunction "PP_TP") (pintype "input"))
      (node (ref "X1") (pin "15") (pinfunction "15_15") (pintype "passive"))
    )
    (net (code "16") (name "Net-(2C-KL)") (class "Default")
      (node (ref "2") (pin "11") (pinfunction "KL_11") (pintype "passive"))
      (node (ref "IC7") (pin "16") (pinfunction "O1_16") (pintype "open_collector"))
      (node (ref "R18") (pin "2") (pinfunction "2_2") (pintype "passive"))
      (node (ref "R19") (pin "1") (pinfunction "1_1") (pintype "passive"))
      (node (ref "TP26") (pin "TP") (pinfunction "PP_TP") (pintype "input"))
    )
    (net (code "17") (name "Net-(2D-KL)") (class "Default")
      (node (ref "2") (pin "12") (pinfunction "KL_12") (pintype "passive"))
      (node (ref "R46") (pin "1") (pinfunction "1_1") (pintype "passive"))
      (node (ref "TP13") (pin "TP") (pinfunction "PP_TP") (pintype "input"))
    )
    (net (code "18") (name "Net-(2E-KL)") (class "Default")
      (node (ref "2") (pin "2") (pinfunction "KL_2") (pintype "passive"))
      (node (ref "D9") (pin "2") (pinfunction "-_2") (pintype "passive"))
      (node (ref "LED2") (pin "K") (pinfunction "C_K") (pintype "passive"))
      (node (ref "TP16") (pin "TP") (pinfunction "PP_TP") (pintype "input"))
      (node (ref "X1") (pin "12") (pinfunction "12_12") (pintype "passive"))
    )
    (net (code "19") (name "Net-(2F-KL)") (class "Default")
      (node (ref "2") (pin "3") (pinfunction "KL_3") (pintype "passive"))
      (node (ref "D8") (pin "2") (pinfunction "-_2") (pintype "passive"))
      (node (ref "LED3") (pin "K") (pinfunction "C_K") (pintype "passive"))
      (node (ref "TP17") (pin "TP") (pinfunction "PP_TP") (pintype "input"))
      (node (ref "X1") (pin "11") (pinfunction "11_11") (pintype "passive"))
    )
    (net (code "20") (name "Net-(2G-KL)") (class "Default")
      (node (ref "2") (pin "4") (pinfunction "KL_4") (pintype "passive"))
      (node (ref "D7") (pin "2") (pinfunction "-_2") (pintype "passive"))
      (node (ref "LED4") (pin "K") (pinfunction "C_K") (pintype "passive"))
      (node (ref "TP18") (pin "TP") (pinfunction "PP_TP") (pintype "input"))
      (node (ref "X1") (pin "10") (pinfunction "10_10") (pintype "passive"))
    )
    (net (code "21") (name "Net-(2H-KL)") (class "Default")
      (node (ref "2") (pin "5") (pinfunction "KL_5") (pintype "passive"))
      (node (ref "D6") (pin "2") (pinfunction "-_2") (pintype "passive"))
      (node (ref "LED5") (pin "K") (pinfunction "C_K") (pintype "passive"))
      (node (ref "TP19") (pin "TP") (pinfunction "PP_TP") (pintype "input"))
      (node (ref "X1") (pin "9") (pinfunction "9_9") (pintype "passive"))
    )
    (net (code "22") (name "Net-(2I-KL)") (class "Default")
      (node (ref "2") (pin "6") (pinfunction "KL_6") (pintype "passive"))
      (node (ref "JP5") (pin "2") (pinfunction "2_2") (pintype "passive"))
      (node (ref "TP21") (pin "TP") (pinfunction "PP_TP") (pintype "input"))
    )
    (net (code "23") (name "Net-(2J-KL)") (class "Default")
      (node (ref "2") (pin "7") (pinfunction "KL_7") (pintype "passive"))
      (node (ref "LED1") (pin "A") (pinfunction "A_A") (pintype "passive"))
      (node (ref "TP22") (pin "TP") (pinfunction "PP_TP") (pintype "input"))
      (node (ref "X1") (pin "8") (pinfunction "8_8") (pintype "passive"))
    )
    (net (code "24") (name "Net-(2K-KL)") (class "Default")
      (node (ref "2") (pin "8") (pinfunction "KL_8") (pintype "passive"))
      (node (ref "D10") (pin "2") (pinfunction "-_2") (pintype "passive"))
      (node (ref "LED6") (pin "K") (pinfunction "C_K") (pintype "passive"))
      (node (ref "TP23") (pin "TP") (pinfunction "PP_TP") (pintype "input"))
      (node (ref "X1") (pin "14") (pinfunction "14_14") (pintype "passive"))
    )
    (net (code "25") (name "Net-(2L-KL)") (class "Default")
      (node (ref "2") (pin "9") (pinfunction "KL_9") (pintype "passive"))
      (node (ref "D7") (pin "1") (pinfunction "+_1") (pintype "passive"))
      (node (ref "D8") (pin "1") (pinfunction "+_1") (pintype "passive"))
      (node (ref "JP2") (pin "1") (pinfunction "1_1") (pintype "passive"))
      (node (ref "JP3") (pin "2") (pinfunction "2_2") (pintype "passive"))
      (node (ref "TP24") (pin "TP") (pinfunction "PP_TP") (pintype "input"))
    )
    (net (code "26") (name "Net-(C3-Pad1)") (class "Default")
      (node (ref "C3") (pin "1") (pinfunction "1_1") (pintype "passive"))
      (node (ref "R12") (pin "1") (pinfunction "1_1") (pintype "passive"))
      (node (ref "R8") (pin "1") (pinfunction "1_1") (pintype "passive"))
    )
    (net (code "27") (name "Net-(C7-Pad1)") (class "Default")
      (node (ref "C7") (pin "1") (pinfunction "1_1") (pintype "passive"))
      (node (ref "R25") (pin "1") (pinfunction "1_1") (pintype "passive"))
      (node (ref "R30") (pin "2") (pinfunction "2_2") (pintype "passive"))
    )
    (net (code "28") (name "Net-(D4-PadC)") (class "Default")
      (node (ref "D4") (pin "C") (pinfunction "C_C") (pintype "passive"))
      (node (ref "R5") (pin "2") (pinfunction "2_2") (pintype "passive"))
      (node (ref "X1") (pin "22") (pinfunction "22_22") (pintype "passive"))
    )
    (net (code "29") (name "Net-(D5--)") (class "Default")
      (node (ref "D5") (pin "2") (pinfunction "-_2") (pintype "passive"))
      (node (ref "Q4") (pin "2") (pinfunction "C_2") (pintype "passive"))
      (node (ref "START") (pin "TP") (pinfunction "PP_TP") (pintype "input"))
      (node (ref "X1") (pin "5") (pinfunction "5_5") (pintype "passive"))
    )
    (net (code "30") (name "Net-(D6-+)") (class "Default")
      (node (ref "D6") (pin "1") (pinfunction "+_1") (pintype "passive"))
      (node (ref "R27") (pin "1") (pinfunction "1_1") (pintype "passive"))
    )
    (net (code "31") (name "Net-(D9-+)") (class "Default")
      (node (ref "D9") (pin "1") (pinfunction "+_1") (pintype "passive"))
      (node (ref "JP2") (pin "2") (pinfunction "2_2") (pintype "passive"))
    )
    (net (code "32") (name "Net-(D10-+)") (class "Default")
      (node (ref "D10") (pin "1") (pinfunction "+_1") (pintype "passive"))
      (node (ref "JP3") (pin "1") (pinfunction "1_1") (pintype "passive"))
    )
    (net (code "33") (name "Net-(D11-+)") (class "Default")
      (node (ref "D11") (pin "1") (pinfunction "+_1") (pintype "passive"))
      (node (ref "R33") (pin "1") (pinfunction "1_1") (pintype "passive"))
    )
    (net (code "34") (name "Net-(D11--)") (class "Default")
      (node (ref "D11") (pin "2") (pinfunction "-_2") (pintype "passive"))
      (node (ref "IC8") (pin "2") (pinfunction "OUT_2") (pintype "open_collector"))
      (node (ref "JP5") (pin "1") (pinfunction "1_1") (pintype "passive"))
      (node (ref "Q7") (pin "1") (pinfunction "G_1") (pintype "passive"))
      (node (ref "R35") (pin "2") (pinfunction "2_2") (pintype "passive"))
    )
    (net (code "35") (name "Net-(D12-+)") (class "Default")
      (node (ref "D12") (pin "1") (pinfunction "+_1") (pintype "passive"))
      (node (ref "R40") (pin "1") (pinfunction "1_1") (pintype "passive"))
    )
    (net (code "36") (name "Net-(D12--)") (class "Default")
      (node (ref "C9") (pin "2") (pinfunction "2_2") (pintype "passive"))
      (node (ref "D12") (pin "2") (pinfunction "-_2") (pintype "passive"))
      (node (ref "IC10") (pin "2") (pinfunction "TR_2") (pintype "input"))
      (node (ref "IC10") (pin "6") (pinfunction "THR_6") (pintype "input"))
      (node (ref "IC6") (pin "6") (pinfunction "D2_6") (pintype "passive"))
      (node (ref "R41") (pin "1") (pinfunction "1_1") (pintype "passive"))
    )
    (net (code "37") (name "Net-(IC1A-+IN)") (class "Default")
      (node (ref "C1") (pin "1") (pinfunction "1_1") (pintype "passive"))
      (node (ref "IC1") (pin "3") (pinfunction "+IN_3") (pintype "input"))
      (node (ref "R5") (pin "1") (pinfunction "1_1") (pintype "passive"))
    )
    (net (code "38") (name "Net-(IC1A--IN)") (class "Default")
      (node (ref "IC1") (pin "2") (pinfunction "-IN_2") (pintype "input"))
      (node (ref "R7") (pin "2") (pinfunction "2_2") (pintype "passive"))
    )
    (net (code "39") (name "Net-(IC1A-OUT)") (class "Default")
      (node (ref "IC1") (pin "1") (pinfunction "OUT_1") (pintype "output"))
      (node (ref "R8") (pin "2") (pinfunction "2_2") (pintype "passive"))
    )
    (net (code "40") (name "Net-(IC1B-+IN)") (class "Default")
      (node (ref "IC1") (pin "5") (pinfunction "+IN_5") (pintype "input"))
      (node (ref "R12") (pin "2") (pinfunction "2_2") (pintype "passive"))
      (node (ref "R17") (pin "2") (pinfunction "2_2") (pintype "passive"))
    )
    (net (code "41") (name "Net-(IC1B--IN)") (class "Default")
      (node (ref "IC1") (pin "6") (pinfunction "-IN_6") (pintype "input"))
      (node (ref "R13") (pin "1") (pinfunction "1_1") (pintype "passive"))
      (node (ref "R14") (pin "2") (pinfunction "2_2") (pintype "passive"))
    )
    (net (code "42") (name "Net-(IC1B-OUT)") (class "Default")
      (node (ref "IC1") (pin "7") (pinfunction "OUT_7") (pintype "output"))
      (node (ref "R16") (pin "1") (pinfunction "1_1") (pintype "passive"))
      (node (ref "R17") (pin "1") (pinfunction "1_1") (pintype "passive"))
    )
    (net (code "43") (name "Net-(IC5A-A)") (class "Default")
      (node (ref "IC5") (pin "10") (pinfunction "A_10") (pintype "input"))
      (node (ref "IC6") (pin "1") (pinfunction "D1_1") (pintype "passive"))
      (node (ref "R11") (pin "1") (pinfunction "1_1") (pintype "passive"))
      (node (ref "X1") (pin "4") (pinfunction "4_4") (pintype "passive"))
      (node (ref "X3") (pin "2") (pinfunction "S_2") (pintype "passive"))
    )
    (net (code "44") (name "Net-(IC5A-B)") (class "Default")
      (node (ref "IC5") (pin "13") (pinfunction "B_13") (pintype "input"))
      (node (ref "IC6") (pin "4") (pinfunction "D4_4") (pintype "passive"))
      (node (ref "R10") (pin "1") (pinfunction "1_1") (pintype "passive"))
      (node (ref "X1") (pin "3") (pinfunction "3_3") (pintype "passive"))
      (node (ref "X3") (pin "3") (pinfunction "S_3") (pintype "passive"))
    )
    (net (code "45") (name "Net-(IC5A-C)") (class "Default")
      (node (ref "IC5") (pin "12") (pinfunction "C_12") (pintype "input"))
      (node (ref "IC6") (pin "3") (pinfunction "D3_3") (pintype "passive"))
      (node (ref "R9") (pin "1") (pinfunction "1_1") (pintype "passive"))
      (node (ref "X1") (pin "2") (pinfunction "2_2") (pintype "passive"))
      (node (ref "X3") (pin "4") (pinfunction "S_4") (pintype "passive"))
    )
    (net (code "46") (name "Net-(IC5A-Q0)") (class "Default")
      (node (ref "IC5") (pin "3") (pinfunction "Q0_3") (pintype "output"))
      (node (ref "IC7") (pin "1") (pinfunction "I1_1") (pintype "input"))
      (node (ref "IC7") (pin "2") (pinfunction "I2_2") (pintype "input"))
      (node (ref "Q6") (pin "1") (pinfunction "G_1") (pintype "passive"))
    )
    (net (code "47") (name "Net-(IC5A-Q1)") (class "Default")
      (node (ref "IC5") (pin "14") (pinfunction "Q1_14") (pintype "output"))
      (node (ref "IC7") (pin "6") (pinfunction "I6_6") (pintype "input"))
    )
    (net (code "48") (name "Net-(IC5A-Q2)") (class "Default")
      (node (ref "IC5") (pin "2") (pinfunction "Q2_2") (pintype "output"))
      (node (ref "IC7") (pin "7") (pinfunction "I7_7") (pintype "input"))
    )
    (net (code "49") (name "Net-(IC5A-Q3)") (class "Default")
      (node (ref "IC5") (pin "15") (pinfunction "Q3_15") (pintype "output"))
      (node (ref "IC7") (pin "5") (pinfunction "I5_5") (pintype "input"))
    )
    (net (code "50") (name "Net-(IC5A-Q4)") (class "Default")
      (node (ref "IC5") (pin "1") (pinfunction "Q4_1") (pintype "output"))
      (node (ref "IC7") (pin "4") (pinfunction "I4_4") (pintype "input"))
    )
    (net (code "51") (name "Net-(IC5A-Q5)") (class "Default")
      (node (ref "IC5") (pin "6") (pinfunction "Q5_6") (pintype "output"))
      (node (ref "IC7") (pin "3") (pinfunction "I3_3") (pintype "input"))
    )
    (net (code "52") (name "Net-(IC7-O2)") (class "Default")
      (node (ref "IC7") (pin "15") (pinfunction "O2_15") (pintype "open_collector"))
      (node (ref "R28") (pin "1") (pinfunction "1_1") (pintype "passive"))
    )
    (net (code "53") (name "Net-(IC8A-+IN)") (class "Default")
      (node (ref "IC8") (pin "5") (pinfunction "+IN_5") (pintype "input"))
      (node (ref "R31") (pin "1") (pinfunction "1_1") (pintype "passive"))
      (node (ref "R32") (pin "2") (pinfunction "2_2") (pintype "passive"))
      (node (ref "R33") (pin "2") (pinfunction "2_2") (pintype "passive"))
    )
    (net (code "54") (name "Net-(IC8A--IN)") (class "Default")
      (node (ref "C8") (pin "1") (pinfunction "1_1") (pintype "passive"))
      (node (ref "IC8") (pin "4") (pinfunction "-IN_4") (pintype "input"))
      (node (ref "R30") (pin "1") (pinfunction "1_1") (pintype "passive"))
    )
    (net (code "55") (name "Net-(IC8B-+IN)") (class "Default")
      (node (ref "IC8") (pin "7") (pinfunction "+IN_7") (pintype "input"))
      (node (ref "R21") (pin "1") (pinfunction "1_1") (pintype "passive"))
      (node (ref "R22") (pin "1") (pinfunction "1_1") (pintype "passive"))
    )
    (net (code "56") (name "Net-(IC8B--IN)") (class "Default")
      (node (ref "IC8") (pin "6") (pinfunction "-IN_6") (pintype "input"))
      (node (ref "IC8") (pin "8") (pinfunction "-IN_8") (pintype "input"))
      (node (ref "R20") (pin "1") (pinfunction "1_1") (pintype "passive"))
    )
    (net (code "57") (name "Net-(IC8B-OUT)") (class "Default")
      (node (ref "IC8") (pin "1") (pinfunction "OUT_1") (pintype "open_collector"))
      (node (ref "R24") (pin "2") (pinfunction "2_2") (pintype "passive"))
      (node (ref "R25") (pin "2") (pinfunction "2_2") (pintype "passive"))
    )
    (net (code "58") (name "Net-(IC8C-+IN)") (class "Default")
      (node (ref "C5") (pin "1") (pinfunction "1_1") (pintype "passive"))
      (node (ref "IC8") (pin "9") (pinfunction "+IN_9") (pintype "input"))
      (node (ref "R22") (pin "2") (pinfunction "2_2") (pintype "passive"))
      (node (ref "R23") (pin "2") (pinfunction "2_2") (pintype "passive"))
    )
    (net (code "59") (name "Net-(IC8C-OUT)") (class "Default")
      (node (ref "C6") (pin "2") (pinfunction "2_2") (pintype "passive"))
      (node (ref "IC8") (pin "14") (pinfunction "OUT_14") (pintype "open_collector"))
      (node (ref "R26") (pin "2") (pinfunction "2_2") (pintype "passive"))
    )
    (net (code "60") (name "Net-(IC9-ADJ)") (class "Default")
      (node (ref "IC9") (pin "1") (pinfunction "ADJ_1") (pintype "input"))
      (node (ref "R20") (pin "2") (pinfunction "2_2") (pintype "passive"))
      (node (ref "R34") (pin "1") (pinfunction "1_1") (pintype "passive"))
      (node (ref "X1") (pin "7") (pinfunction "7_7") (pintype "passive"))
    )
    (net (code "61") (name "Net-(IC9-VI)") (class "Default")
      (node (ref "IC9") (pin "3") (pinfunction "VI_3") (pintype "input"))
      (node (ref "Q5") (pin "2") (pinfunction "C_2") (pintype "passive"))
    )
    (net (code "62") (name "Net-(IC9-VO)") (class "Default")
      (node (ref "IC9") (pin "2") (pinfunction "VO_2") (pintype "passive"))
      (node (ref "R34") (pin "2") (pinfunction "2_2") (pintype "passive"))
    )
    (net (code "63") (name "Net-(IC10-CV)") (class "Default")
      (node (ref "IC10") (pin "5") (pinfunction "CV_5") (pintype "input"))
      (node (ref "R44") (pin "2") (pinfunction "2_2") (pintype "passive"))
    )
    (net (code "64") (name "Net-(IC10-Q)") (class "Default")
      (node (ref "IC10") (pin "3") (pinfunction "Q_3") (pintype "output"))
      (node (ref "IC11") (pin "12") (pinfunction "A_12") (pintype "input"))
      (node (ref "R44") (pin "1") (pinfunction "1_1") (pintype "passive"))
    )
    (net (code "65") (name "Net-(IC11B-B)") (class "Default")
      (node (ref "IC11") (pin "11") (pinfunction "B_11") (pintype "input"))
      (node (ref "IC11") (pin "9") (pinfunction "~{Q}_9") (pintype "output"))
      (node (ref "R46") (pin "2") (pinfunction "2_2") (pintype "passive"))
    )
    (net (code "66") (name "Net-(IC11B-T2)") (class "Default")
      (node (ref "C10") (pin "1") (pinfunction "1_1") (pintype "passive"))
      (node (ref "IC11") (pin "14") (pinfunction "T2_14") (pintype "input"))
      (node (ref "R45") (pin "1") (pinfunction "1_1") (pintype "passive"))
    )
    (net (code "67") (name "Net-(JP1-Pad1)") (class "Default")
      (node (ref "JP1") (pin "1") (pinfunction "1_1") (pintype "passive"))
      (node (ref "R19") (pin "2") (pinfunction "2_2") (pintype "passive"))
    )
    (net (code "68") (name "Net-(JP4-Pad2)") (class "Default")
      (node (ref "JP4") (pin "2") (pinfunction "2_2") (pintype "passive"))
      (node (ref "R36") (pin "2") (pinfunction "2_2") (pintype "passive"))
      (node (ref "R37") (pin "2") (pinfunction "2_2") (pintype "passive"))
      (node (ref "SJ1") (pin "2") (pinfunction "2_2") (pintype "passive"))
    )
    (net (code "69") (name "Net-(JP5-Pad3)") (class "Default")
      (node (ref "JP5") (pin "3") (pinfunction "3_3") (pintype "passive"))
      (node (ref "R38") (pin "1") (pinfunction "1_1") (pintype "passive"))
      (node (ref "R39") (pin "1") (pinfunction "1_1") (pintype "passive"))
    )
    (net (code "70") (name "Net-(LED1-C)") (class "Default")
      (node (ref "LED1") (pin "K") (pinfunction "C_K") (pintype "passive"))
      (node (ref "R43") (pin "1") (pinfunction "1_1") (pintype "passive"))
    )
    (net (code "71") (name "Net-(LED2-PadA)") (class "Default")
      (node (ref "LED2") (pin "A") (pinfunction "A_A") (pintype "passive"))
      (node (ref "LED3") (pin "A") (pinfunction "A_A") (pintype "passive"))
      (node (ref "LED4") (pin "A") (pinfunction "A_A") (pintype "passive"))
      (node (ref "LED5") (pin "A") (pinfunction "A_A") (pintype "passive"))
      (node (ref "LED6") (pin "A") (pinfunction "A_A") (pintype "passive"))
      (node (ref "R42") (pin "1") (pinfunction "1_1") (pintype "passive"))
    )
    (net (code "72") (name "Net-(Q1-B)") (class "Default")
      (node (ref "Q1") (pin "1") (pinfunction "B_1") (pintype "passive"))
      (node (ref "Q2") (pin "1") (pinfunction "B_1") (pintype "passive"))
      (node (ref "Q2") (pin "2") (pinfunction "C_2") (pintype "passive"))
      (node (ref "R1") (pin "1") (pinfunction "1_1") (pintype "passive"))
      (node (ref "R3") (pin "1") (pinfunction "1_1") (pintype "passive"))
      (node (ref "R4") (pin "1") (pinfunction "1_1") (pintype "passive"))
      (node (ref "X2") (pin "2") (pinfunction "S_2") (pintype "passive"))
    )
    (net (code "73") (name "Net-(Q1-E)") (class "Default")
      (node (ref "Q1") (pin "3") (pinfunction "E_3") (pintype "passive"))
      (node (ref "R2") (pin "2") (pinfunction "2_2") (pintype "passive"))
    )
    (net (code "74") (name "Net-(Q2-E)") (class "Default")
      (node (ref "Q2") (pin "3") (pinfunction "E_3") (pintype "passive"))
      (node (ref "R6") (pin "2") (pinfunction "2_2") (pintype "passive"))
    )
    (net (code "75") (name "Net-(Q3-B)") (class "Default")
      (node (ref "Q3") (pin "1") (pinfunction "B_1") (pintype "passive"))
      (node (ref "R16") (pin "2") (pinfunction "2_2") (pintype "passive"))
    )
    (net (code "76") (name "Net-(Q3-C)") (class "Default")
      (node (ref "Q3") (pin "2") (pinfunction "C_2") (pintype "passive"))
      (node (ref "R15") (pin "2") (pinfunction "2_2") (pintype "passive"))
      (node (ref "R18") (pin "1") (pinfunction "1_1") (pintype "passive"))
    )
    (net (code "77") (name "Net-(Q4-B)") (class "Default")
      (node (ref "Q4") (pin "1") (pinfunction "B_1") (pintype "passive"))
      (node (ref "R28") (pin "2") (pinfunction "2_2") (pintype "passive"))
    )
    (net (code "78") (name "Net-(Q5-B)") (class "Default")
      (node (ref "Q5") (pin "1") (pinfunction "B_1") (pintype "passive"))
      (node (ref "R26") (pin "1") (pinfunction "1_1") (pintype "passive"))
    )
    (net (code "79") (name "Net-(Q7-D)") (class "Default")
      (node (ref "Q7") (pin "3") (pinfunction "D_3") (pintype "passive"))
      (node (ref "R38") (pin "2") (pinfunction "2_2") (pintype "passive"))
    )
    (net (code "80") (name "Net-(R15-Pad1)") (class "Default")
      (node (ref "R15") (pin "1") (pinfunction "1_1") (pintype "passive"))
      (node (ref "X1") (pin "21") (pinfunction "21_21") (pintype "passive"))
    )
    (net (code "81") (name "Net-(R27-Pad2)") (class "Default")
      (node (ref "R27") (pin "2") (pinfunction "2_2") (pintype "passive"))
      (node (ref "R29") (pin "1") (pinfunction "1_1") (pintype "passive"))
    )
    (net (code "82") (name "Net-(R40-Pad2)") (class "Default")
      (node (ref "R40") (pin "2") (pinfunction "2_2") (pintype "passive"))
      (node (ref "X1") (pin "16") (pinfunction "16_16") (pintype "passive"))
    )
    (net (code "83") (name "VCC") (class "Default")
      (node (ref "6V") (pin "TP") (pinfunction "PP_TP") (pintype "input"))
      (node (ref "C4") (pin "1") (pinfunction "1_1") (pintype "passive"))
      (node (ref "IC1") (pin "8") (pinfunction "V+_8") (pintype "power_in"))
      (node (ref "IC2") (pin "1") (pinfunction "OUT_1") (pintype "passive"))
      (node (ref "IC3") (pin "OUT") (pinfunction "OUT_OUT") (pintype "passive"))
      (node (ref "IC8") (pin "3") (pinfunction "V+_3") (pintype "power_in"))
      (node (ref "R13") (pin "2") (pinfunction "2_2") (pintype "passive"))
      (node (ref "R21") (pin "2") (pinfunction "2_2") (pintype "passive"))
      (node (ref "R24") (pin "1") (pinfunction "1_1") (pintype "passive"))
      (node (ref "R31") (pin "2") (pinfunction "2_2") (pintype "passive"))
      (node (ref "R42") (pin "2") (pinfunction "2_2") (pintype "passive"))
    )
    (net (code "84") (name "unconnected-(IC5A-Q6-Pad7)") (class "Default")
      (node (ref "IC5") (pin "7") (pinfunction "Q6_7") (pintype "output"))
    )
    (net (code "85") (name "unconnected-(IC5A-Q7-Pad4)") (class "Default")
      (node (ref "IC5") (pin "4") (pinfunction "Q7_4") (pintype "output"))
    )
    (net (code "86") (name "unconnected-(IC5A-Q8-Pad9)") (class "Default")
      (node (ref "IC5") (pin "9") (pinfunction "Q8_9") (pintype "output"))
    )
    (net (code "87") (name "unconnected-(IC5A-Q9-Pad5)") (class "Default")
      (node (ref "IC5") (pin "5") (pinfunction "Q9_5") (pintype "output"))
    )
    (net (code "88") (name "unconnected-(IC8D-OUT-Pad13)") (class "Default")
      (node (ref "IC8") (pin "13") (pinfunction "OUT_13") (pintype "open_collector"))
    )
    (net (code "89") (name "unconnected-(IC10-DIS-Pad7)") (class "Default")
      (node (ref "IC10") (pin "7") (pinfunction "DIS_7") (pintype "input"))
    )
    (net (code "90") (name "unconnected-(IC11A-Q-Pad6)") (class "Default")
      (node (ref "IC11") (pin "6") (pinfunction "Q_6") (pintype "output"))
    )
    (net (code "91") (name "unconnected-(IC11A-T2-Pad2)") (class "Default")
      (node (ref "IC11") (pin "2") (pinfunction "T2_2") (pintype "input"))
    )
    (net (code "92") (name "unconnected-(IC11A-~{Q}-Pad7)") (class "Default")
      (node (ref "IC11") (pin "7") (pinfunction "~{Q}_7") (pintype "output"))
    )
    (net (code "93") (name "unconnected-(IC11B-Q-Pad10)") (class "Default")
      (node (ref "IC11") (pin "10") (pinfunction "Q_10") (pintype "output"))
    )
    (net (code "94") (name "unconnected-(X1-Pad20)") (class "Default")
      (node (ref "X1") (pin "20") (pinfunction "20_20") (pintype "passive"))
    )
    (net (code "95") (name "unconnected-(X1-Pad24)") (class "Default")
      (node (ref "X1") (pin "24") (pinfunction "24_24") (pintype "passive"))
    )
  )
)
